# openSX70-dongle_SEEED_v401.net
KiCad netlist of a schematic drawn in EAGLE
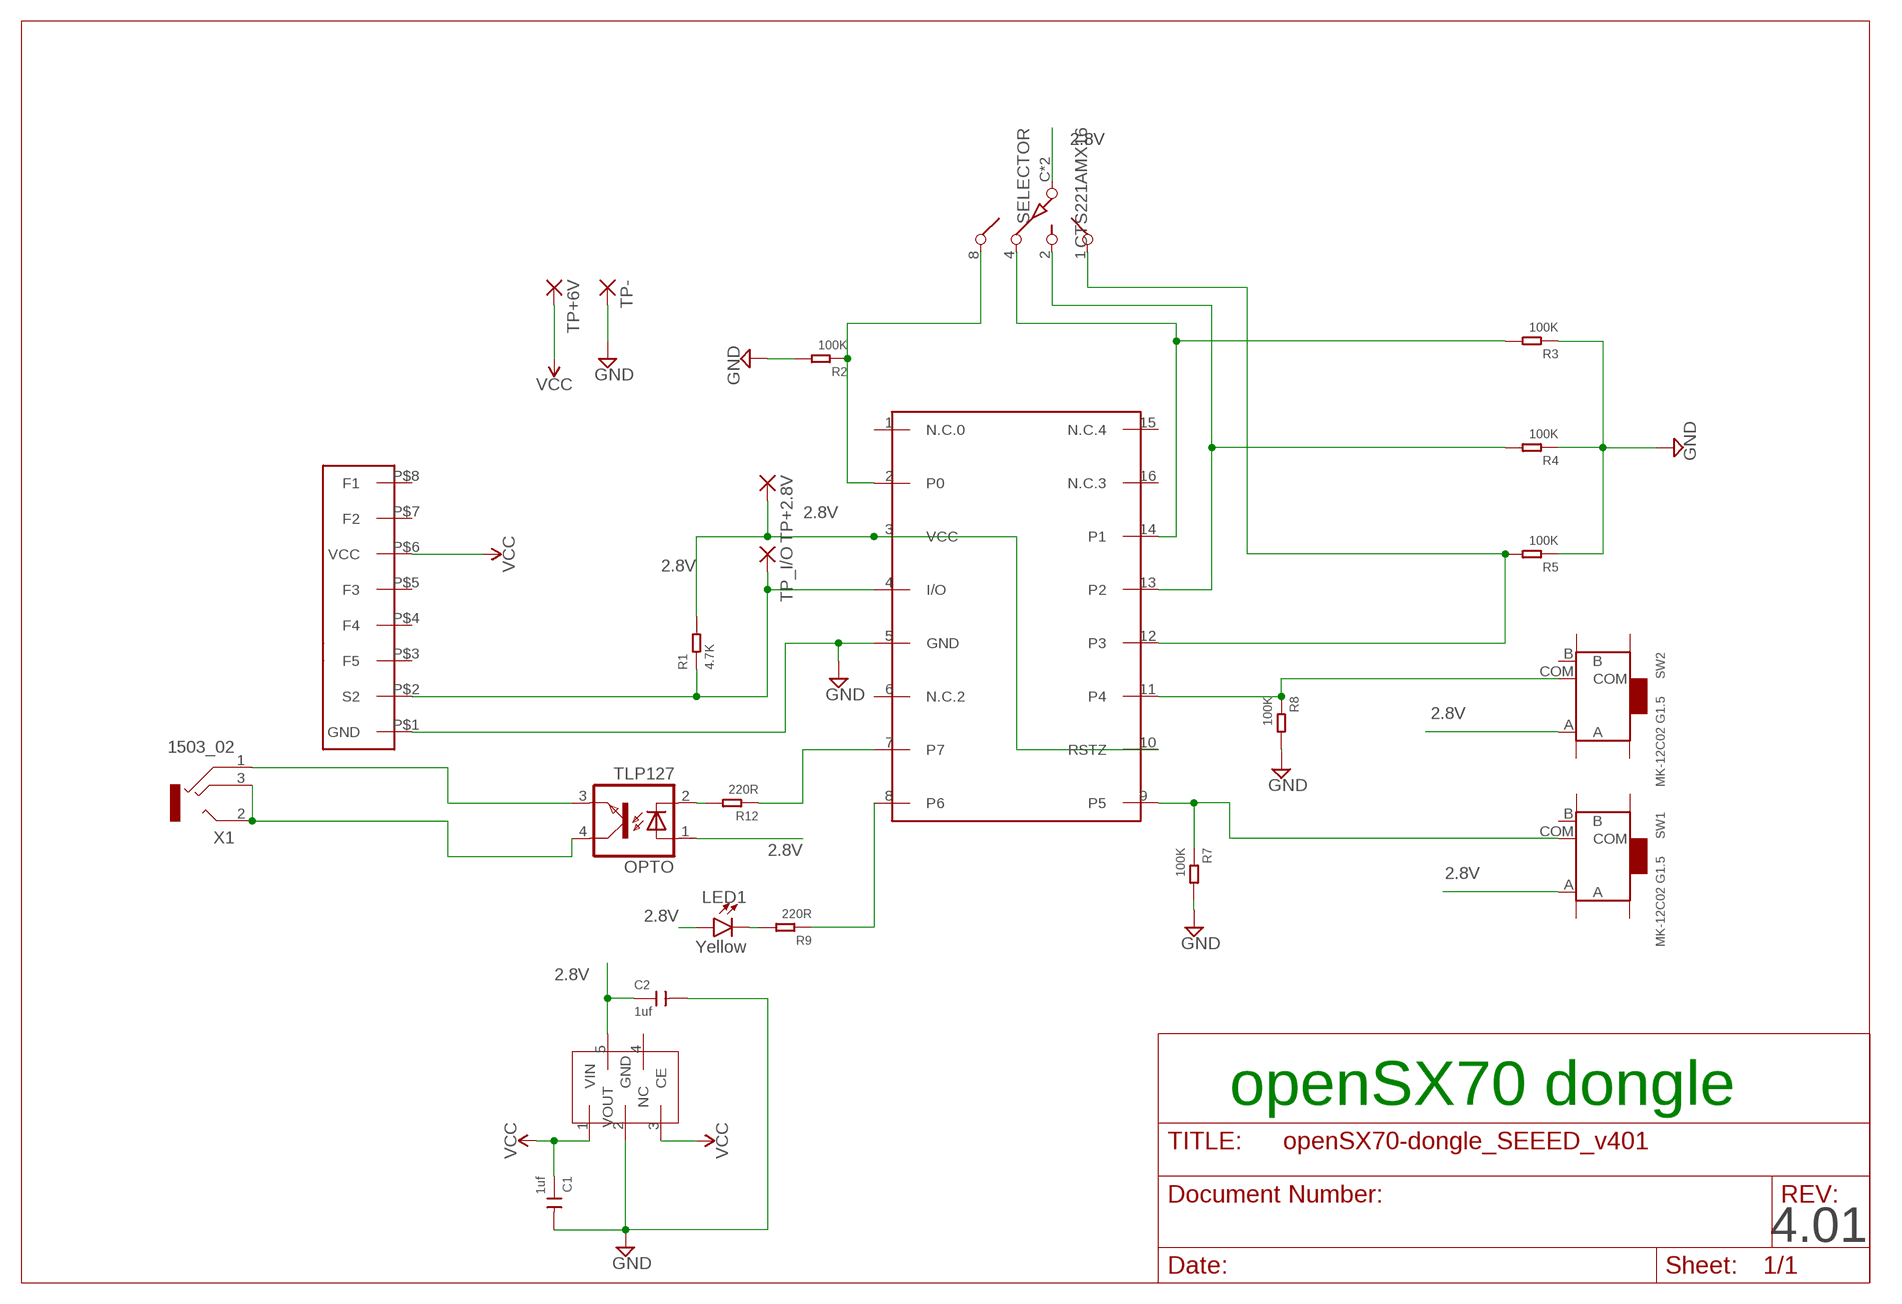
[diagram p0: schematic, sheet 1]

(export (version "E")
  (design (tool "Eeschema 10.0.6"))
  (components
    (comp (ref "C1")
      (value "1uf")
      (footprint "eagle-import:C0603")
      (fields (field (name "MPN") "CC0603KRX7R8BB105"))
      (libsource (lib "eagle-import") (part "CERAMIC-1UF-25V-10%-X7R(0603)"))
    )
    (comp (ref "C2")
      (value "1uf")
      (footprint "eagle-import:C0603")
      (fields (field (name "MPN") "CC0603KRX7R8BB105"))
      (libsource (lib "eagle-import") (part "CERAMIC-1UF-25V-10%-X7R(0603)"))
    )
    (comp (ref "DS2408")
      (value "DS2408")
      (footprint "eagle-import:SO16")
      (libsource (lib "eagle-import") (part "DS2408"))
    )
    (comp (ref "LED1")
      (value "Yellow")
      (footprint "eagle-import:LED-1206")
      (libsource (lib "eagle-import") (part "LED-YELLOWLILYPAD"))
    )
    (comp (ref "OPTO")
      (value "TLP127")
      (footprint "eagle-import:SO-4")
      (libsource (lib "eagle-import") (part "TLP127"))
    )
    (comp (ref "R1")
      (value "4.7K")
      (footprint "eagle-import:R0603")
      (fields (field (name "MPN") "RC0603JR-074K7L"))
      (libsource (lib "eagle-import") (part "SMD-RES-4.7K-5%-1/10W(0603)"))
    )
    (comp (ref "R2")
      (value "100K")
      (footprint "eagle-import:R0603")
      (fields (field (name "MPN") "RC0603FR-07100KL"))
      (libsource (lib "eagle-import") (part "SMD-RES-100K-1%-1/10W(0603)"))
    )
    (comp (ref "R3")
      (value "100K")
      (footprint "eagle-import:R0603")
      (fields (field (name "MPN") "RC0603FR-07100KL"))
      (libsource (lib "eagle-import") (part "SMD-RES-100K-1%-1/10W(0603)"))
    )
    (comp (ref "R4")
      (value "100K")
      (footprint "eagle-import:R0603")
      (fields (field (name "MPN") "RC0603FR-07100KL"))
      (libsource (lib "eagle-import") (part "SMD-RES-100K-1%-1/10W(0603)"))
    )
    (comp (ref "R5")
      (value "100K")
      (footprint "eagle-import:R0603")
      (fields (field (name "MPN") "RC0603FR-07100KL"))
      (libsource (lib "eagle-import") (part "SMD-RES-100K-1%-1/10W(0603)"))
    )
    (comp (ref "R7")
      (value "100K")
      (footprint "eagle-import:R0603")
      (fields (field (name "MPN") "RC0603FR-07100KL"))
      (libsource (lib "eagle-import") (part "SMD-RES-100K-1%-1/10W(0603)"))
    )
    (comp (ref "R8")
      (value "100K")
      (footprint "eagle-import:R0603")
      (fields (field (name "MPN") "RC0603FR-07100KL"))
      (libsource (lib "eagle-import") (part "SMD-RES-100K-1%-1/10W(0603)"))
    )
    (comp (ref "R9")
      (value "220R")
      (footprint "eagle-import:R0603")
      (fields (field (name "MPN") "RC0603JR-07220RL"))
      (libsource (lib "eagle-import") (part "SMD-RES-220R-5%-1/10W(0603)"))
    )
    (comp (ref "R12")
      (value "220R")
      (footprint "eagle-import:R0603")
      (fields (field (name "MPN") "RC0603JR-07220RL"))
      (libsource (lib "eagle-import") (part "SMD-RES-220R-5%-1/10W(0603)"))
    )
    (comp (ref "REG")
      (value "NCP4688")
      (footprint "eagle-import:SOT-23-5")
      (libsource (lib "eagle-import") (part "NCP4688"))
    )
    (comp (ref "SELECTOR")
      (value "CTS221AMX16")
      (footprint "eagle-import:CTS221AMX16")
      (libsource (lib "eagle-import") (part "CTS221AMX16"))
    )
    (comp (ref "SW1")
      (value "MK-12C02 G1.5")
      (footprint "eagle-import:SW7-SMD-L6.7X2.7X3.2MM")
      (libsource (lib "eagle-import") (part "SMD-TOGGLE-SWITCH-ON-ON(3+4P-6.7X2.7MM)"))
    )
    (comp (ref "SW2")
      (value "MK-12C02 G1.5")
      (footprint "eagle-import:SW7-SMD-L6.7X2.7X3.2MM")
      (libsource (lib "eagle-import") (part "SMD-TOGGLE-SWITCH-ON-ON(3+4P-6.7X2.7MM)"))
    )
    (comp (ref "TP+2.8V")
      (value "SMD2")
      (footprint "eagle-import:SMD1,27-2,54")
      (libsource (lib "eagle-import") (part "SMD2"))
    )
    (comp (ref "TP+6V")
      (value "SMD2")
      (footprint "eagle-import:SMD1,27-2,54")
      (libsource (lib "eagle-import") (part "SMD2"))
    )
    (comp (ref "TP-")
      (value "SMD2")
      (footprint "eagle-import:SMD1,27-2,54")
      (libsource (lib "eagle-import") (part "SMD2"))
    )
    (comp (ref "TP_I/O")
      (value "SMD2")
      (footprint "eagle-import:SMD1,27-2,54")
      (libsource (lib "eagle-import") (part "SMD2"))
    )
    (comp (ref "U$1")
      (value "FLASH-EDGE-CONNECTOR")
      (footprint "eagle-import:FLASH-EDGE-8")
      (libsource (lib "eagle-import") (part "FLASH-EDGE-CONNECTOR"))
    )
    (comp (ref "X1")
      (value "1503_02")
      (footprint "eagle-import:1503_02")
      (libsource (lib "eagle-import") (part "1503_02"))
    )
  )
  (nets
    (net (code "1") (name "/2.8V") (class "Default")
      (node (ref "C2") (pin "1") (pinfunction "1_1") (pintype "passive"))
      (node (ref "DS2408") (pin "10") (pinfunction "RSTZ_10") (pintype "bidirectional"))
      (node (ref "DS2408") (pin "3") (pinfunction "VCC_3") (pintype "bidirectional"))
      (node (ref "LED1") (pin "A") (pinfunction "A_A") (pintype "passive"))
      (node (ref "OPTO") (pin "1") (pinfunction "A_1") (pintype "passive"))
      (node (ref "R1") (pin "2") (pinfunction "2_2") (pintype "passive"))
      (node (ref "REG") (pin "5") (pinfunction "VOUT_5") (pintype "bidirectional"))
      (node (ref "SELECTOR") (pin "C") (pinfunction "C_C") (pintype "passive"))
      (node (ref "SELECTOR") (pin "C2") (pinfunction "C_C2") (pintype "passive"))
      (node (ref "SW1") (pin "A") (pinfunction "A_A") (pintype "bidirectional"))
      (node (ref "SW2") (pin "A") (pinfunction "A_A") (pintype "bidirectional"))
      (node (ref "TP+2.8V") (pin "1") (pinfunction "P_1") (pintype "passive"))
    )
    (net (code "2") (name "GND") (class "Default")
      (node (ref "C1") (pin "2") (pinfunction "2_2") (pintype "passive"))
      (node (ref "C2") (pin "2") (pinfunction "2_2") (pintype "passive"))
      (node (ref "DS2408") (pin "5") (pinfunction "GND_5") (pintype "bidirectional"))
      (node (ref "R2") (pin "2") (pinfunction "2_2") (pintype "passive"))
      (node (ref "R3") (pin "1") (pinfunction "1_1") (pintype "passive"))
      (node (ref "R4") (pin "1") (pinfunction "1_1") (pintype "passive"))
      (node (ref "R5") (pin "1") (pinfunction "1_1") (pintype "passive"))
      (node (ref "R7") (pin "2") (pinfunction "2_2") (pintype "passive"))
      (node (ref "R8") (pin "2") (pinfunction "2_2") (pintype "passive"))
      (node (ref "REG") (pin "2") (pinfunction "GND_2") (pintype "bidirectional"))
      (node (ref "TP-") (pin "1") (pinfunction "P_1") (pintype "passive"))
      (node (ref "U$1") (pin "P$1") (pinfunction "GND_P$1") (pintype "bidirectional"))
    )
    (net (code "3") (name "Net-(DS2408-I{slash}O)") (class "Default")
      (node (ref "DS2408") (pin "4") (pinfunction "I/O_4") (pintype "bidirectional"))
      (node (ref "R1") (pin "1") (pinfunction "1_1") (pintype "passive"))
      (node (ref "TP_I/O") (pin "1") (pinfunction "P_1") (pintype "passive"))
      (node (ref "U$1") (pin "P$2") (pinfunction "S2_P$2") (pintype "bidirectional"))
    )
    (net (code "4") (name "Net-(DS2408-P0)") (class "Default")
      (node (ref "DS2408") (pin "2") (pinfunction "P0_2") (pintype "bidirectional"))
      (node (ref "R2") (pin "1") (pinfunction "1_1") (pintype "passive"))
      (node (ref "SELECTOR") (pin "8") (pinfunction "8_8") (pintype "passive"))
    )
    (net (code "5") (name "Net-(DS2408-P1)") (class "Default")
      (node (ref "DS2408") (pin "14") (pinfunction "P1_14") (pintype "bidirectional"))
      (node (ref "R3") (pin "2") (pinfunction "2_2") (pintype "passive"))
      (node (ref "SELECTOR") (pin "4") (pinfunction "4_4") (pintype "passive"))
    )
    (net (code "6") (name "Net-(DS2408-P2)") (class "Default")
      (node (ref "DS2408") (pin "13") (pinfunction "P2_13") (pintype "bidirectional"))
      (node (ref "R4") (pin "2") (pinfunction "2_2") (pintype "passive"))
      (node (ref "SELECTOR") (pin "2") (pinfunction "2_2") (pintype "passive"))
    )
    (net (code "7") (name "Net-(DS2408-P3)") (class "Default")
      (node (ref "DS2408") (pin "12") (pinfunction "P3_12") (pintype "bidirectional"))
      (node (ref "R5") (pin "2") (pinfunction "2_2") (pintype "passive"))
      (node (ref "SELECTOR") (pin "1") (pinfunction "1_1") (pintype "passive"))
    )
    (net (code "8") (name "Net-(DS2408-P4)") (class "Default")
      (node (ref "DS2408") (pin "11") (pinfunction "P4_11") (pintype "bidirectional"))
      (node (ref "R8") (pin "1") (pinfunction "1_1") (pintype "passive"))
      (node (ref "SW2") (pin "COM") (pinfunction "COM_COM") (pintype "bidirectional"))
    )
    (net (code "9") (name "Net-(DS2408-P5)") (class "Default")
      (node (ref "DS2408") (pin "9") (pinfunction "P5_9") (pintype "bidirectional"))
      (node (ref "R7") (pin "1") (pinfunction "1_1") (pintype "passive"))
      (node (ref "SW1") (pin "COM") (pinfunction "COM_COM") (pintype "bidirectional"))
    )
    (net (code "10") (name "Net-(DS2408-P6)") (class "Default")
      (node (ref "DS2408") (pin "8") (pinfunction "P6_8") (pintype "bidirectional"))
      (node (ref "R9") (pin "1") (pinfunction "1_1") (pintype "passive"))
    )
    (net (code "11") (name "Net-(DS2408-P7)") (class "Default")
      (node (ref "DS2408") (pin "7") (pinfunction "P7_7") (pintype "bidirectional"))
      (node (ref "R12") (pin "1") (pinfunction "1_1") (pintype "passive"))
    )
    (net (code "12") (name "Net-(LED1-PadC)") (class "Default")
      (node (ref "LED1") (pin "C") (pinfunction "C_C") (pintype "passive"))
      (node (ref "R9") (pin "2") (pinfunction "2_2") (pintype "passive"))
    )
    (net (code "13") (name "Net-(OPTO-C)") (class "Default")
      (node (ref "OPTO") (pin "2") (pinfunction "C_2") (pintype "passive"))
      (node (ref "R12") (pin "2") (pinfunction "2_2") (pintype "passive"))
    )
    (net (code "14") (name "Net-(OPTO-COL)") (class "Default")
      (node (ref "OPTO") (pin "4") (pinfunction "COL_4") (pintype "passive"))
      (node (ref "X1") (pin "2") (pinfunction "2_2") (pintype "passive"))
      (node (ref "X1") (pin "3") (pinfunction "3_3") (pintype "passive"))
    )
    (net (code "15") (name "Net-(OPTO-EMIT)") (class "Default")
      (node (ref "OPTO") (pin "3") (pinfunction "EMIT_3") (pintype "passive"))
      (node (ref "X1") (pin "1") (pinfunction "1_1") (pintype "passive"))
    )
    (net (code "16") (name "VCC") (class "Default")
      (node (ref "C1") (pin "1") (pinfunction "1_1") (pintype "passive"))
      (node (ref "REG") (pin "1") (pinfunction "VIN_1") (pintype "bidirectional"))
      (node (ref "REG") (pin "3") (pinfunction "CE_3") (pintype "bidirectional"))
      (node (ref "TP+6V") (pin "1") (pinfunction "P_1") (pintype "passive"))
      (node (ref "U$1") (pin "P$6") (pinfunction "VCC_P$6") (pintype "bidirectional"))
    )
    (net (code "17") (name "unconnected-(DS2408-N.C.0-Pad1)") (class "Default")
      (node (ref "DS2408") (pin "1") (pinfunction "N.C.0_1") (pintype "bidirectional"))
    )
    (net (code "18") (name "unconnected-(DS2408-N.C.2-Pad6)") (class "Default")
      (node (ref "DS2408") (pin "6") (pinfunction "N.C.2_6") (pintype "bidirectional"))
    )
    (net (code "19") (name "unconnected-(DS2408-N.C.3-Pad16)") (class "Default")
      (node (ref "DS2408") (pin "16") (pinfunction "N.C.3_16") (pintype "bidirectional"))
    )
    (net (code "20") (name "unconnected-(DS2408-N.C.4-Pad15)") (class "Default")
      (node (ref "DS2408") (pin "15") (pinfunction "N.C.4_15") (pintype "bidirectional"))
    )
    (net (code "21") (name "unconnected-(REG-NC-Pad4)") (class "Default")
      (node (ref "REG") (pin "4") (pinfunction "NC_4") (pintype "bidirectional"))
    )
    (net (code "22") (name "unconnected-(SW1-PadB)") (class "Default")
      (node (ref "SW1") (pin "B") (pinfunction "B_B") (pintype "bidirectional"))
    )
    (net (code "23") (name "unconnected-(SW1-PadSS1)") (class "Default")
      (node (ref "SW1") (pin "SS1") (pinfunction "SS1_SS1") (pintype "bidirectional"))
    )
    (net (code "24") (name "unconnected-(SW1-PadSS2)") (class "Default")
      (node (ref "SW1") (pin "SS2") (pinfunction "SS2_SS2") (pintype "bidirectional"))
    )
    (net (code "25") (name "unconnected-(SW1-PadSS3)") (class "Default")
      (node (ref "SW1") (pin "SS3") (pinfunction "SS3_SS3") (pintype "bidirectional"))
    )
    (net (code "26") (name "unconnected-(SW1-PadSS4)") (class "Default")
      (node (ref "SW1") (pin "SS4") (pinfunction "SS4_SS4") (pintype "bidirectional"))
    )
    (net (code "27") (name "unconnected-(SW2-PadB)") (class "Default")
      (node (ref "SW2") (pin "B") (pinfunction "B_B") (pintype "bidirectional"))
    )
    (net (code "28") (name "unconnected-(SW2-PadSS1)") (class "Default")
      (node (ref "SW2") (pin "SS1") (pinfunction "SS1_SS1") (pintype "bidirectional"))
    )
    (net (code "29") (name "unconnected-(SW2-PadSS2)") (class "Default")
      (node (ref "SW2") (pin "SS2") (pinfunction "SS2_SS2") (pintype "bidirectional"))
    )
    (net (code "30") (name "unconnected-(SW2-PadSS3)") (class "Default")
      (node (ref "SW2") (pin "SS3") (pinfunction "SS3_SS3") (pintype "bidirectional"))
    )
    (net (code "31") (name "unconnected-(SW2-PadSS4)") (class "Default")
      (node (ref "SW2") (pin "SS4") (pinfunction "SS4_SS4") (pintype "bidirectional"))
    )
    (net (code "32") (name "unconnected-(U$1-F1-PadP$8)") (class "Default")
      (node (ref "U$1") (pin "P$8") (pinfunction "F1_P$8") (pintype "bidirectional"))
    )
    (net (code "33") (name "unconnected-(U$1-F2-PadP$7)") (class "Default")
      (node (ref "U$1") (pin "P$7") (pinfunction "F2_P$7") (pintype "bidirectional"))
    )
    (net (code "34") (name "unconnected-(U$1-F3-PadP$5)") (class "Default")
      (node (ref "U$1") (pin "P$5") (pinfunction "F3_P$5") (pintype "bidirectional"))
    )
    (net (code "35") (name "unconnected-(U$1-F4-PadP$4)") (class "Default")
      (node (ref "U$1") (pin "P$4") (pinfunction "F4_P$4") (pintype "bidirectional"))
    )
    (net (code "36") (name "unconnected-(U$1-F5-PadP$3)") (class "Default")
      (node (ref "U$1") (pin "P$3") (pinfunction "F5_P$3") (pintype "bidirectional"))
    )
    (net (code "37") (name "unconnected-(X1-2-Pad2@2)") (class "Default")
      (node (ref "X1") (pin "2@2") (pinfunction "2_2@2") (pintype "passive"))
    )
  )
)
